# Connectors.net
KiCad netlist of a schematic drawn in Altium Designer
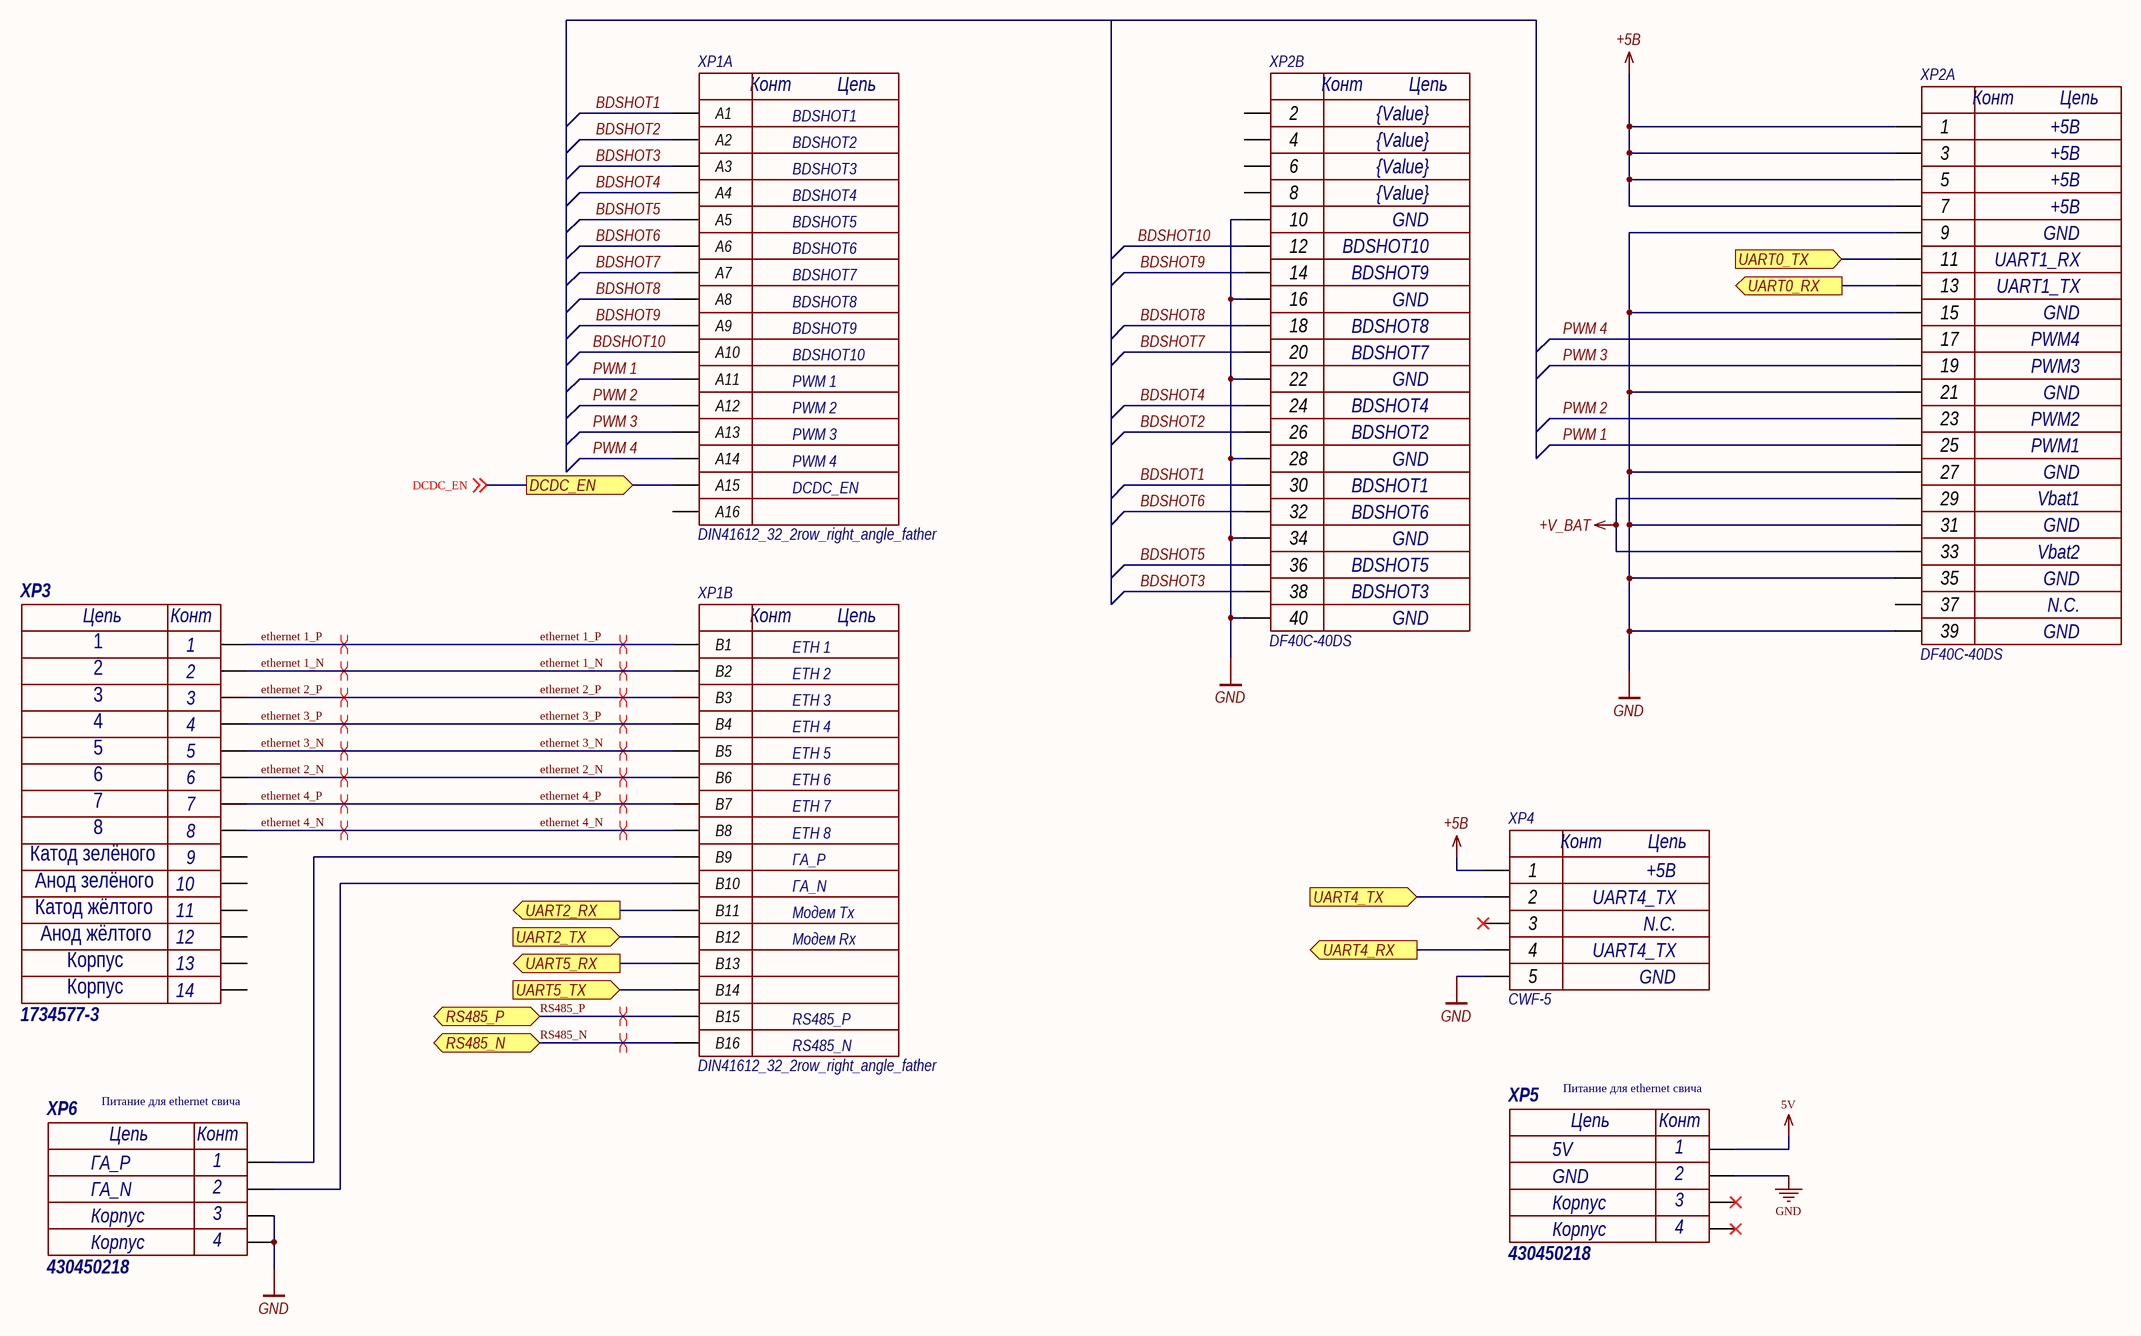
[diagram p0: Connectors.SchDoc]

(export (version "E")
  (design (tool "Eeschema 10.0.6"))
  (components
    (comp (ref "XP1")
      (value "DIN41612_32_2row_right_angle_father")
      (footprint "DIN41612_32_2row_right_angle_father")
      (libsource (lib "Hydrolib") (part "DIN41612_32_2row"))
    )
    (comp (ref "XP2")
      (value "DF40C-40DS")
      (footprint "DF40C-40DS")
      (description "Разъем плата-плата 40 пинов, папа, шаг 0.4мм")
      (fields
        (field (name "VALUE17") "Vbat2")
        (field (name "VALUE20") "GND")
        (field (name "VALUE19") "N.C.")
        (field (name "VALUE18") "GND")
        (field (name "VALUE16") "GND")
        (field (name "VALUE15") "Vbat1")
        (field (name "VALUE14") "GND")
        (field (name "VALUE13") "PWM1")
        (field (name "VALUE12") "PWM2")
        (field (name "VALUE11") "GND")
        (field (name "VALUE10") "PWM3")
        (field (name "VALUE9") "PWM4")
        (field (name "VALUE8") "GND")
        (field (name "VALUE7") "UART1_TX")
        (field (name "VALUE6") "UART1_RX")
        (field (name "VALUE5") "GND")
        (field (name "VALUE4") "+5В")
        (field (name "VALUE3") "+5В")
        (field (name "VALUE2") "+5В")
        (field (name "VALUE1") "+5В")
      )
      (libsource (lib "Hydrolib") (part "Conn_40pin_double"))
    )
    (comp (ref "XP3")
      (value "1734577-3")
      (footprint "1-1734577-3-rj45-8p8c")
      (description "Модульный разъем, Cat3, RJ45, Гнездо, 8 контакт(-ов), 8 вывод(-ов), 1 порт(-ов)")
      (fields (field (name "PART NUMBER") "1-1734577-3-rj45-8p8c"))
      (libsource (lib "Hydrolib") (part "1-1734577-3-rj45-8p8c"))
    )
    (comp (ref "XP4")
      (value "CWF-5")
      (footprint "CWF-5")
      (description "5-пиновый разъем с ключом")
      (fields
        (field (name "VALUE1") "+5В")
        (field (name "VALUE2") "UART4_TX")
        (field (name "VALUE3") "N.C.")
        (field (name "VALUE4") "UART4_TX")
        (field (name "VALUE5") "GND")
      )
      (libsource (lib "Hydrolib") (part "Conn_5pin"))
    )
    (comp (ref "XP5")
      (value "430450218")
      (footprint "Molex_430450218")
      (fields
        (field (name "VALUE3") "Корпус")
        (field (name "VALUE2") "GND")
        (field (name "VALUE4") "Корпус")
        (field (name "VALUE1") "5V")
        (field (name "PART NUMBER") "Molex_430450218")
        (field (name "PARAMETER 1") "Питание для ethernet свича")
      )
      (libsource (lib "Hydrolib") (part "Molex_430450218"))
    )
    (comp (ref "XP6")
      (value "430450218")
      (footprint "Molex_430450218")
      (fields
        (field (name "VALUE3") "Корпус")
        (field (name "VALUE2") "ГА_N")
        (field (name "VALUE4") "Корпус")
        (field (name "VALUE1") "ГА_P")
        (field (name "PART NUMBER") "Molex_430450218")
        (field (name "PARAMETER 1") "Питание для ethernet свича")
      )
      (libsource (lib "Hydrolib") (part "Molex_430450218"))
    )
  )
  (nets
    (net (code "1") (name "+5В") (class "Default")
      (node (ref "XP2") (pin "1") (pinfunction "1_1") (pintype "passive"))
      (node (ref "XP2") (pin "3") (pinfunction "3_3") (pintype "passive"))
      (node (ref "XP2") (pin "5") (pinfunction "5_5") (pintype "passive"))
      (node (ref "XP2") (pin "7") (pinfunction "7_7") (pintype "passive"))
      (node (ref "XP4") (pin "1") (pinfunction "1_1") (pintype "passive"))
    )
    (net (code "2") (name "+V_BAT") (class "Default")
      (node (ref "XP2") (pin "29") (pinfunction "29_29") (pintype "passive"))
      (node (ref "XP2") (pin "33") (pinfunction "33_33") (pintype "passive"))
    )
    (net (code "3") (name "/BDSHOT1") (class "Default")
      (node (ref "XP1") (pin "A1") (pinfunction "A1_A1") (pintype "passive"))
      (node (ref "XP2") (pin "30") (pinfunction "30_30") (pintype "passive"))
    )
    (net (code "4") (name "/BDSHOT2") (class "Default")
      (node (ref "XP1") (pin "A2") (pinfunction "A2_A2") (pintype "passive"))
      (node (ref "XP2") (pin "26") (pinfunction "26_26") (pintype "passive"))
    )
    (net (code "5") (name "/BDSHOT3") (class "Default")
      (node (ref "XP1") (pin "A3") (pinfunction "A3_A3") (pintype "passive"))
      (node (ref "XP2") (pin "38") (pinfunction "38_38") (pintype "passive"))
    )
    (net (code "6") (name "/BDSHOT4") (class "Default")
      (node (ref "XP1") (pin "A4") (pinfunction "A4_A4") (pintype "passive"))
      (node (ref "XP2") (pin "24") (pinfunction "24_24") (pintype "passive"))
    )
    (net (code "7") (name "/BDSHOT5") (class "Default")
      (node (ref "XP1") (pin "A5") (pinfunction "A5_A5") (pintype "passive"))
      (node (ref "XP2") (pin "36") (pinfunction "36_36") (pintype "passive"))
    )
    (net (code "8") (name "/BDSHOT6") (class "Default")
      (node (ref "XP1") (pin "A6") (pinfunction "A6_A6") (pintype "passive"))
      (node (ref "XP2") (pin "32") (pinfunction "32_32") (pintype "passive"))
    )
    (net (code "9") (name "/BDSHOT7") (class "Default")
      (node (ref "XP1") (pin "A7") (pinfunction "A7_A7") (pintype "passive"))
      (node (ref "XP2") (pin "20") (pinfunction "20_20") (pintype "passive"))
    )
    (net (code "10") (name "/BDSHOT8") (class "Default")
      (node (ref "XP1") (pin "A8") (pinfunction "A8_A8") (pintype "passive"))
      (node (ref "XP2") (pin "18") (pinfunction "18_18") (pintype "passive"))
    )
    (net (code "11") (name "/BDSHOT9") (class "Default")
      (node (ref "XP1") (pin "A9") (pinfunction "A9_A9") (pintype "passive"))
      (node (ref "XP2") (pin "14") (pinfunction "14_14") (pintype "passive"))
    )
    (net (code "12") (name "/BDSHOT10") (class "Default")
      (node (ref "XP1") (pin "A10") (pinfunction "A10_A10") (pintype "passive"))
      (node (ref "XP2") (pin "12") (pinfunction "12_12") (pintype "passive"))
    )
    (net (code "13") (name "/PWM 1") (class "Default")
      (node (ref "XP1") (pin "A11") (pinfunction "A11_A11") (pintype "passive"))
      (node (ref "XP2") (pin "25") (pinfunction "25_25") (pintype "passive"))
    )
    (net (code "14") (name "/PWM 2") (class "Default")
      (node (ref "XP1") (pin "A12") (pinfunction "A12_A12") (pintype "passive"))
      (node (ref "XP2") (pin "23") (pinfunction "23_23") (pintype "passive"))
    )
    (net (code "15") (name "/PWM 3") (class "Default")
      (node (ref "XP1") (pin "A13") (pinfunction "A13_A13") (pintype "passive"))
      (node (ref "XP2") (pin "19") (pinfunction "19_19") (pintype "passive"))
    )
    (net (code "16") (name "/PWM 4") (class "Default")
      (node (ref "XP1") (pin "A14") (pinfunction "A14_A14") (pintype "passive"))
      (node (ref "XP2") (pin "17") (pinfunction "17_17") (pintype "passive"))
    )
    (net (code "17") (name "/RS485_N") (class "Default")
      (node (ref "XP1") (pin "B16") (pinfunction "B16_B16") (pintype "passive"))
    )
    (net (code "18") (name "/RS485_P") (class "Default")
      (node (ref "XP1") (pin "B15") (pinfunction "B15_B15") (pintype "passive"))
    )
    (net (code "19") (name "/UART0_RX") (class "Default")
      (node (ref "XP2") (pin "13") (pinfunction "13_13") (pintype "passive"))
    )
    (net (code "20") (name "/UART0_TX") (class "Default")
      (node (ref "XP2") (pin "11") (pinfunction "11_11") (pintype "passive"))
    )
    (net (code "21") (name "/UART2_RX") (class "Default")
      (node (ref "XP1") (pin "B11") (pinfunction "B11_B11") (pintype "passive"))
    )
    (net (code "22") (name "/UART2_TX") (class "Default")
      (node (ref "XP1") (pin "B12") (pinfunction "B12_B12") (pintype "passive"))
    )
    (net (code "23") (name "/UART4_RX") (class "Default")
      (node (ref "XP4") (pin "4") (pinfunction "4_4") (pintype "passive"))
    )
    (net (code "24") (name "/UART4_TX") (class "Default")
      (node (ref "XP4") (pin "2") (pinfunction "2_2") (pintype "passive"))
    )
    (net (code "25") (name "/UART5_RX") (class "Default")
      (node (ref "XP1") (pin "B13") (pinfunction "B13_B13") (pintype "passive"))
    )
    (net (code "26") (name "/UART5_TX") (class "Default")
      (node (ref "XP1") (pin "B14") (pinfunction "B14_B14") (pintype "passive"))
    )
    (net (code "27") (name "/ethernet 1_N") (class "Default")
      (node (ref "XP1") (pin "B2") (pinfunction "B2_B2") (pintype "passive"))
      (node (ref "XP3") (pin "2") (pinfunction "2_2") (pintype "passive"))
    )
    (net (code "28") (name "/ethernet 1_P") (class "Default")
      (node (ref "XP1") (pin "B1") (pinfunction "B1_B1") (pintype "passive"))
      (node (ref "XP3") (pin "1") (pinfunction "1_1") (pintype "passive"))
    )
    (net (code "29") (name "/ethernet 2_N") (class "Default")
      (node (ref "XP1") (pin "B6") (pinfunction "B6_B6") (pintype "passive"))
      (node (ref "XP3") (pin "6") (pinfunction "6_6") (pintype "passive"))
    )
    (net (code "30") (name "/ethernet 2_P") (class "Default")
      (node (ref "XP1") (pin "B3") (pinfunction "B3_B3") (pintype "passive"))
      (node (ref "XP3") (pin "3") (pinfunction "3_3") (pintype "passive"))
    )
    (net (code "31") (name "/ethernet 3_N") (class "Default")
      (node (ref "XP1") (pin "B5") (pinfunction "B5_B5") (pintype "passive"))
      (node (ref "XP3") (pin "5") (pinfunction "5_5") (pintype "passive"))
    )
    (net (code "32") (name "/ethernet 3_P") (class "Default")
      (node (ref "XP1") (pin "B4") (pinfunction "B4_B4") (pintype "passive"))
      (node (ref "XP3") (pin "4") (pinfunction "4_4") (pintype "passive"))
    )
    (net (code "33") (name "/ethernet 4_N") (class "Default")
      (node (ref "XP1") (pin "B8") (pinfunction "B8_B8") (pintype "passive"))
      (node (ref "XP3") (pin "8") (pinfunction "8_8") (pintype "passive"))
    )
    (net (code "34") (name "/ethernet 4_P") (class "Default")
      (node (ref "XP1") (pin "B7") (pinfunction "B7_B7") (pintype "passive"))
      (node (ref "XP3") (pin "7") (pinfunction "7_7") (pintype "passive"))
    )
    (net (code "35") (name "5V") (class "Default")
      (node (ref "XP5") (pin "1") (pinfunction "1_1") (pintype "passive"))
    )
    (net (code "36") (name "DCDC_EN") (class "Default")
      (node (ref "XP1") (pin "A15") (pinfunction "A15_A15") (pintype "passive"))
    )
    (net (code "37") (name "GND") (class "Default")
      (node (ref "XP2") (pin "10") (pinfunction "10_10") (pintype "passive"))
      (node (ref "XP2") (pin "15") (pinfunction "15_15") (pintype "passive"))
      (node (ref "XP2") (pin "16") (pinfunction "16_16") (pintype "passive"))
      (node (ref "XP2") (pin "21") (pinfunction "21_21") (pintype "passive"))
      (node (ref "XP2") (pin "22") (pinfunction "22_22") (pintype "passive"))
      (node (ref "XP2") (pin "27") (pinfunction "27_27") (pintype "passive"))
      (node (ref "XP2") (pin "28") (pinfunction "28_28") (pintype "passive"))
      (node (ref "XP2") (pin "31") (pinfunction "31_31") (pintype "passive"))
      (node (ref "XP2") (pin "34") (pinfunction "34_34") (pintype "passive"))
      (node (ref "XP2") (pin "35") (pinfunction "35_35") (pintype "passive"))
      (node (ref "XP2") (pin "39") (pinfunction "39_39") (pintype "passive"))
      (node (ref "XP2") (pin "40") (pinfunction "40_40") (pintype "passive"))
      (node (ref "XP2") (pin "9") (pinfunction "9_9") (pintype "passive"))
      (node (ref "XP4") (pin "5") (pinfunction "5_5") (pintype "passive"))
      (node (ref "XP5") (pin "2") (pinfunction "2_2") (pintype "passive"))
      (node (ref "XP6") (pin "0") (pinfunction "0_0") (pintype "passive"))
    )
    (net (code "38") (name "Net-(XP1-PadB9)") (class "Default")
      (node (ref "XP1") (pin "B9") (pinfunction "B9_B9") (pintype "passive"))
      (node (ref "XP6") (pin "1") (pinfunction "1_1") (pintype "passive"))
    )
    (net (code "39") (name "Net-(XP1-PadB10)") (class "Default")
      (node (ref "XP1") (pin "B10") (pinfunction "B10_B10") (pintype "passive"))
      (node (ref "XP6") (pin "2") (pinfunction "2_2") (pintype "passive"))
    )
    (net (code "40") (name "unconnected-(XP1-PadA16)") (class "Default")
      (node (ref "XP1") (pin "A16") (pinfunction "A16_A16") (pintype "passive"))
    )
    (net (code "41") (name "unconnected-(XP2-Pad2)") (class "Default")
      (node (ref "XP2") (pin "2") (pinfunction "2_2") (pintype "passive"))
    )
    (net (code "42") (name "unconnected-(XP2-Pad4)") (class "Default")
      (node (ref "XP2") (pin "4") (pinfunction "4_4") (pintype "passive"))
    )
    (net (code "43") (name "unconnected-(XP2-Pad6)") (class "Default")
      (node (ref "XP2") (pin "6") (pinfunction "6_6") (pintype "passive"))
    )
    (net (code "44") (name "unconnected-(XP2-Pad8)") (class "Default")
      (node (ref "XP2") (pin "8") (pinfunction "8_8") (pintype "passive"))
    )
    (net (code "45") (name "unconnected-(XP2-Pad37)") (class "Default")
      (node (ref "XP2") (pin "37") (pinfunction "37_37") (pintype "passive"))
    )
    (net (code "46") (name "unconnected-(XP3-Pad9)") (class "Default")
      (node (ref "XP3") (pin "9") (pinfunction "9_9") (pintype "passive"))
    )
    (net (code "47") (name "unconnected-(XP3-Pad10)") (class "Default")
      (node (ref "XP3") (pin "10") (pinfunction "10_10") (pintype "passive"))
    )
    (net (code "48") (name "unconnected-(XP3-Pad11)") (class "Default")
      (node (ref "XP3") (pin "11") (pinfunction "11_11") (pintype "passive"))
    )
    (net (code "49") (name "unconnected-(XP3-Pad12)") (class "Default")
      (node (ref "XP3") (pin "12") (pinfunction "12_12") (pintype "passive"))
    )
    (net (code "50") (name "unconnected-(XP3-PadMH1)") (class "Default")
      (node (ref "XP3") (pin "MH1") (pinfunction "MH1_MH1") (pintype "passive"))
    )
    (net (code "51") (name "unconnected-(XP3-PadMH2)") (class "Default")
      (node (ref "XP3") (pin "MH2") (pinfunction "MH2_MH2") (pintype "passive"))
    )
    (net (code "52") (name "unconnected-(XP4-Pad3)") (class "Default")
      (node (ref "XP4") (pin "3") (pinfunction "3_3") (pintype "passive+no_connect"))
    )
    (net (code "53") (name "unconnected-(XP5-Pad0)") (class "Default")
      (node (ref "XP5") (pin "0") (pinfunction "0_0") (pintype "passive+no_connect"))
    )
    (net (code "54") (name "unconnected-(XP5-Pad0)_1") (class "Default")
      (node (ref "XP5") (pin "0") (pinfunction "0_0") (pintype "passive+no_connect"))
    )
  )
)
